# board_a-01.net
KiCad netlist of a schematic drawn in EAGLE
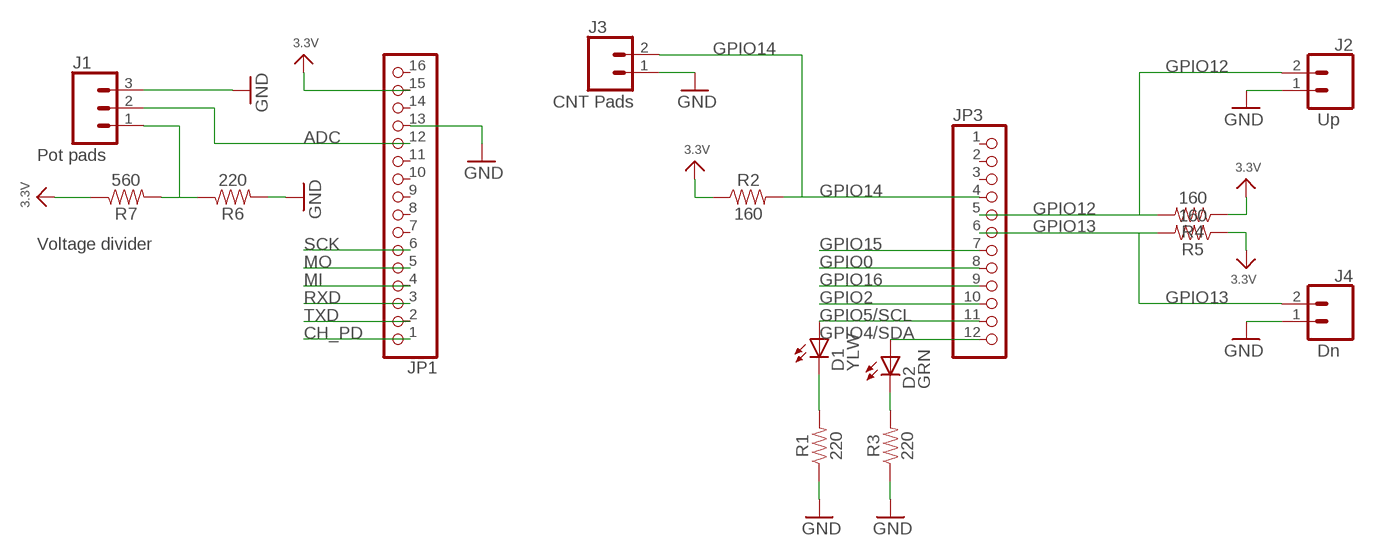
[diagram p0: schematic, sheet 1]

(export (version "E")
  (design (tool "Eeschema 10.0.6"))
  (components
    (comp (ref "D1")
      (value "YLW")
      (footprint "eagle-import:LED3MM")
      (libsource (lib "eagle-import") (part "LED3MM"))
    )
    (comp (ref "D2")
      (value "GRN")
      (footprint "eagle-import:LED3MM")
      (libsource (lib "eagle-import") (part "LED3MM"))
    )
    (comp (ref "J1")
      (value "CONN_03LOCK_LONGPADS")
      (footprint "eagle-import:1X03_LOCK_LONGPADS")
      (libsource (lib "eagle-import") (part "CONN_03LOCK_LONGPADS"))
    )
    (comp (ref "J2")
      (value "CONN_02LOCK_LONGPADS")
      (footprint "eagle-import:1X02_LOCK_LONGPADS")
      (libsource (lib "eagle-import") (part "CONN_02LOCK_LONGPADS"))
    )
    (comp (ref "J3")
      (value "CONN_02LOCK_LONGPADS")
      (footprint "eagle-import:1X02_LOCK_LONGPADS")
      (libsource (lib "eagle-import") (part "CONN_02LOCK_LONGPADS"))
    )
    (comp (ref "J4")
      (value "CONN_02LOCK_LONGPADS")
      (footprint "eagle-import:1X02_LOCK_LONGPADS")
      (libsource (lib "eagle-import") (part "CONN_02LOCK_LONGPADS"))
    )
    (comp (ref "JP1")
      (value "HEADER-1X16ROUND")
      (footprint "eagle-import:1X16_ROUND")
      (libsource (lib "eagle-import") (part "HEADER-1X16ROUND"))
    )
    (comp (ref "JP3")
      (value "HEADER-1X12")
      (footprint "eagle-import:1X12_ROUND")
      (libsource (lib "eagle-import") (part "HEADER-1X12"))
    )
    (comp (ref "R1")
      (value "220")
      (footprint "eagle-import:AXIAL-0.3")
      (libsource (lib "eagle-import") (part "1KOHM-HORIZ-1/4W-1%"))
    )
    (comp (ref "R2")
      (value "160")
      (footprint "eagle-import:AXIAL-0.3")
      (libsource (lib "eagle-import") (part "1KOHM-HORIZ-1/4W-1%"))
    )
    (comp (ref "R3")
      (value "220")
      (footprint "eagle-import:AXIAL-0.3")
      (libsource (lib "eagle-import") (part "1KOHM-HORIZ-1/4W-1%"))
    )
    (comp (ref "R4")
      (value "160")
      (footprint "eagle-import:AXIAL-0.3")
      (libsource (lib "eagle-import") (part "1KOHM-HORIZ-1/4W-1%"))
    )
    (comp (ref "R5")
      (value "160")
      (footprint "eagle-import:AXIAL-0.3")
      (libsource (lib "eagle-import") (part "1KOHM-HORIZ-1/4W-1%"))
    )
    (comp (ref "R6")
      (value "220")
      (footprint "eagle-import:AXIAL-0.3")
      (libsource (lib "eagle-import") (part "1KOHM-HORIZ-1/4W-1%"))
    )
    (comp (ref "R7")
      (value "560")
      (footprint "eagle-import:AXIAL-0.3")
      (libsource (lib "eagle-import") (part "1KOHM-HORIZ-1/4W-1%"))
    )
  )
  (nets
    (net (code "1") (name "/ADC") (class "Default")
      (node (ref "J1") (pin "2") (pinfunction "2_2") (pintype "passive"))
      (node (ref "JP1") (pin "12") (pinfunction "12_12") (pintype "passive"))
    )
    (net (code "2") (name "/CH_PD") (class "Default")
      (node (ref "JP1") (pin "1") (pinfunction "1_1") (pintype "passive"))
    )
    (net (code "3") (name "/GPIO0") (class "Default")
      (node (ref "JP3") (pin "8") (pinfunction "8_8") (pintype "passive"))
    )
    (net (code "4") (name "/GPIO2") (class "Default")
      (node (ref "JP3") (pin "10") (pinfunction "10_10") (pintype "passive"))
    )
    (net (code "5") (name "/GPIO4{slash}SDA") (class "Default")
      (node (ref "D2") (pin "A") (pinfunction "A_A") (pintype "passive"))
      (node (ref "JP3") (pin "12") (pinfunction "12_12") (pintype "passive"))
    )
    (net (code "6") (name "/GPIO5{slash}SCL") (class "Default")
      (node (ref "D1") (pin "A") (pinfunction "A_A") (pintype "passive"))
      (node (ref "JP3") (pin "11") (pinfunction "11_11") (pintype "passive"))
    )
    (net (code "7") (name "/GPIO12") (class "Default")
      (node (ref "J2") (pin "2") (pinfunction "2_2") (pintype "passive"))
      (node (ref "JP3") (pin "5") (pinfunction "5_5") (pintype "passive"))
      (node (ref "R4") (pin "P$2") (pinfunction "2_P$2") (pintype "passive"))
    )
    (net (code "8") (name "/GPIO13") (class "Default")
      (node (ref "J4") (pin "2") (pinfunction "2_2") (pintype "passive"))
      (node (ref "JP3") (pin "6") (pinfunction "6_6") (pintype "passive"))
      (node (ref "R5") (pin "P$2") (pinfunction "2_P$2") (pintype "passive"))
    )
    (net (code "9") (name "/GPIO14") (class "Default")
      (node (ref "J3") (pin "2") (pinfunction "2_2") (pintype "passive"))
      (node (ref "JP3") (pin "4") (pinfunction "4_4") (pintype "passive"))
      (node (ref "R2") (pin "P$2") (pinfunction "2_P$2") (pintype "passive"))
    )
    (net (code "10") (name "/GPIO15") (class "Default")
      (node (ref "JP3") (pin "7") (pinfunction "7_7") (pintype "passive"))
    )
    (net (code "11") (name "/GPIO16") (class "Default")
      (node (ref "JP3") (pin "9") (pinfunction "9_9") (pintype "passive"))
    )
    (net (code "12") (name "/MI") (class "Default")
      (node (ref "JP1") (pin "4") (pinfunction "4_4") (pintype "passive"))
    )
    (net (code "13") (name "/MO") (class "Default")
      (node (ref "JP1") (pin "5") (pinfunction "5_5") (pintype "passive"))
    )
    (net (code "14") (name "/RXD") (class "Default")
      (node (ref "JP1") (pin "3") (pinfunction "3_3") (pintype "passive"))
    )
    (net (code "15") (name "/SCK") (class "Default")
      (node (ref "JP1") (pin "6") (pinfunction "6_6") (pintype "passive"))
    )
    (net (code "16") (name "/TXD") (class "Default")
      (node (ref "JP1") (pin "2") (pinfunction "2_2") (pintype "passive"))
    )
    (net (code "17") (name "3.3V") (class "Default")
      (node (ref "JP1") (pin "15") (pinfunction "15_15") (pintype "passive"))
      (node (ref "R2") (pin "P$1") (pinfunction "1_P$1") (pintype "passive"))
      (node (ref "R4") (pin "P$1") (pinfunction "1_P$1") (pintype "passive"))
      (node (ref "R5") (pin "P$1") (pinfunction "1_P$1") (pintype "passive"))
      (node (ref "R7") (pin "P$1") (pinfunction "1_P$1") (pintype "passive"))
    )
    (net (code "18") (name "GND") (class "Default")
      (node (ref "J1") (pin "3") (pinfunction "3_3") (pintype "passive"))
      (node (ref "J2") (pin "1") (pinfunction "1_1") (pintype "passive"))
      (node (ref "J3") (pin "1") (pinfunction "1_1") (pintype "passive"))
      (node (ref "J4") (pin "1") (pinfunction "1_1") (pintype "passive"))
      (node (ref "JP1") (pin "13") (pinfunction "13_13") (pintype "passive"))
      (node (ref "R1") (pin "P$1") (pinfunction "1_P$1") (pintype "passive"))
      (node (ref "R3") (pin "P$1") (pinfunction "1_P$1") (pintype "passive"))
      (node (ref "R6") (pin "P$2") (pinfunction "2_P$2") (pintype "passive"))
    )
    (net (code "19") (name "Net-(D1-C)") (class "Default")
      (node (ref "D1") (pin "K") (pinfunction "C_K") (pintype "passive"))
      (node (ref "R1") (pin "P$2") (pinfunction "2_P$2") (pintype "passive"))
    )
    (net (code "20") (name "Net-(D2-C)") (class "Default")
      (node (ref "D2") (pin "K") (pinfunction "C_K") (pintype "passive"))
      (node (ref "R3") (pin "P$2") (pinfunction "2_P$2") (pintype "passive"))
    )
    (net (code "21") (name "Net-(R6-1)") (class "Default")
      (node (ref "J1") (pin "1") (pinfunction "1_1") (pintype "passive"))
      (node (ref "R6") (pin "P$1") (pinfunction "1_P$1") (pintype "passive"))
      (node (ref "R7") (pin "P$2") (pinfunction "2_P$2") (pintype "passive"))
    )
    (net (code "22") (name "unconnected-(JP1-Pad7)") (class "Default")
      (node (ref "JP1") (pin "7") (pinfunction "7_7") (pintype "passive"))
    )
    (net (code "23") (name "unconnected-(JP1-Pad8)") (class "Default")
      (node (ref "JP1") (pin "8") (pinfunction "8_8") (pintype "passive"))
    )
    (net (code "24") (name "unconnected-(JP1-Pad9)") (class "Default")
      (node (ref "JP1") (pin "9") (pinfunction "9_9") (pintype "passive"))
    )
    (net (code "25") (name "unconnected-(JP1-Pad10)") (class "Default")
      (node (ref "JP1") (pin "10") (pinfunction "10_10") (pintype "passive"))
    )
    (net (code "26") (name "unconnected-(JP1-Pad11)") (class "Default")
      (node (ref "JP1") (pin "11") (pinfunction "11_11") (pintype "passive"))
    )
    (net (code "27") (name "unconnected-(JP1-Pad14)") (class "Default")
      (node (ref "JP1") (pin "14") (pinfunction "14_14") (pintype "passive"))
    )
    (net (code "28") (name "unconnected-(JP1-Pad16)") (class "Default")
      (node (ref "JP1") (pin "16") (pinfunction "16_16") (pintype "passive"))
    )
    (net (code "29") (name "unconnected-(JP3-Pad1)") (class "Default")
      (node (ref "JP3") (pin "1") (pinfunction "1_1") (pintype "passive"))
    )
    (net (code "30") (name "unconnected-(JP3-Pad2)") (class "Default")
      (node (ref "JP3") (pin "2") (pinfunction "2_2") (pintype "passive"))
    )
    (net (code "31") (name "unconnected-(JP3-Pad3)") (class "Default")
      (node (ref "JP3") (pin "3") (pinfunction "3_3") (pintype "passive"))
    )
  )
)
